# Zio_Ultrasonic_Distance_Sensor.net
KiCad netlist of a schematic drawn in EAGLE
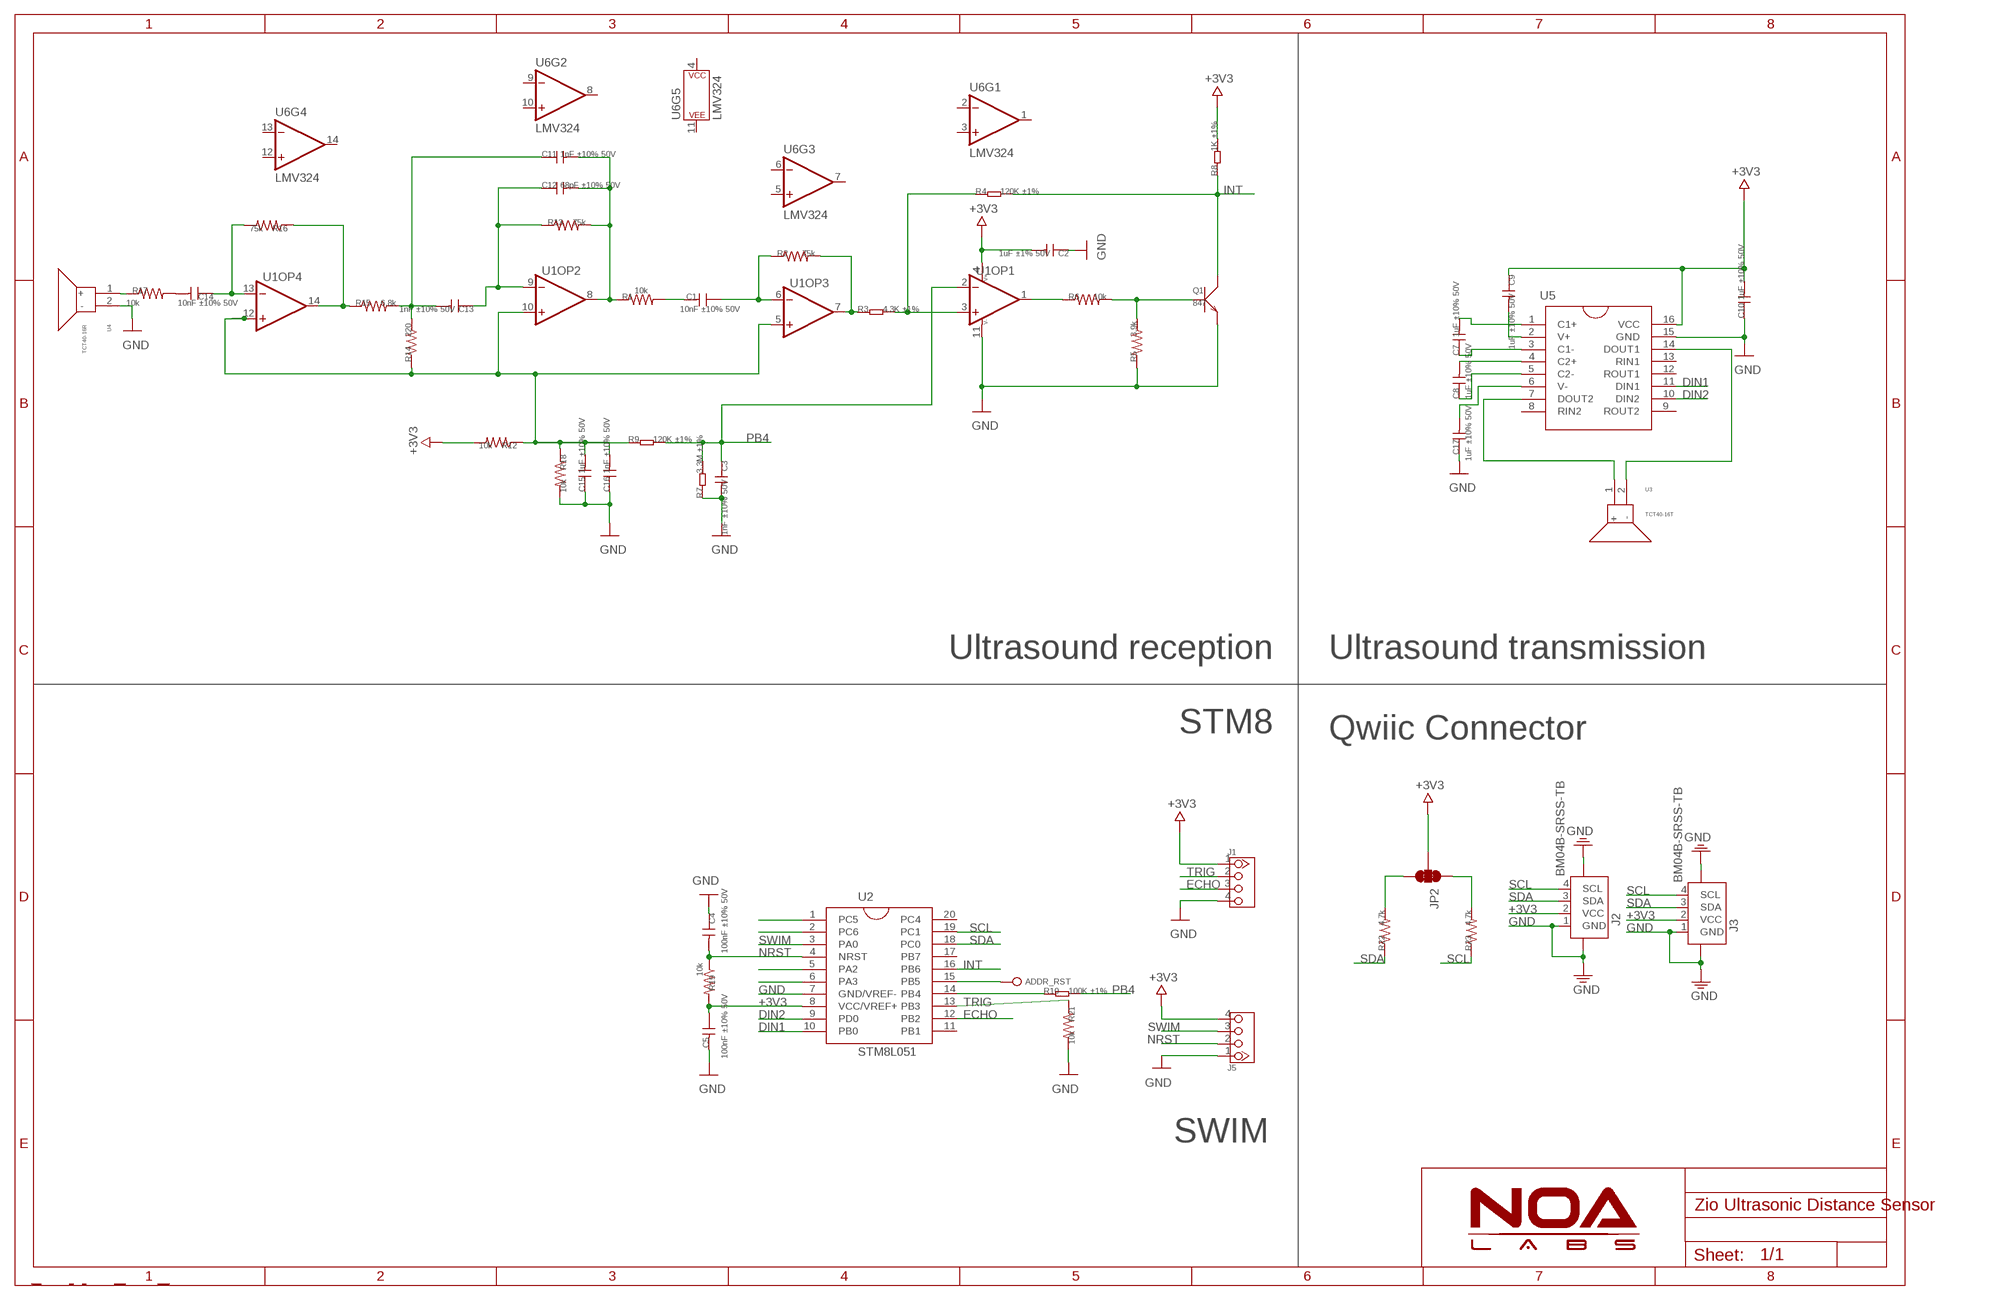
[diagram p0: schematic, sheet 1]

(export (version "E")
  (design (tool "Eeschema 10.0.6"))
  (components
    (comp (ref "ADDR_RST")
      (value "TEST_POINT35MIL")
      (footprint "eagle-import:1P-35MIL")
      (libsource (lib "eagle-import") (part "TEST_POINT35MIL"))
    )
    (comp (ref "C1")
      (value "10nF ±10% 50V")
      (footprint "eagle-import:0603")
      (libsource (lib "eagle-import") (part "C-0603"))
    )
    (comp (ref "C2")
      (value "1uF ±1% 50V")
      (footprint "eagle-import:0603")
      (libsource (lib "eagle-import") (part "C-0603"))
    )
    (comp (ref "C3")
      (value "1nF ±10% 50V")
      (footprint "eagle-import:0603")
      (libsource (lib "eagle-import") (part "C-0603"))
    )
    (comp (ref "C4")
      (value "100nF ±10% 50V")
      (footprint "eagle-import:0603")
      (libsource (lib "eagle-import") (part "C-0603"))
    )
    (comp (ref "C5")
      (value "100nF ±10% 50V")
      (footprint "eagle-import:0603")
      (libsource (lib "eagle-import") (part "C-0603"))
    )
    (comp (ref "C7")
      (value "1uF ±10% 50V")
      (footprint "eagle-import:0603")
      (libsource (lib "eagle-import") (part "C-0603"))
    )
    (comp (ref "C8")
      (value "1uF ±10% 50V")
      (footprint "eagle-import:0603")
      (libsource (lib "eagle-import") (part "C-0603"))
    )
    (comp (ref "C9")
      (value "1uF ±10% 50V")
      (footprint "eagle-import:0603")
      (libsource (lib "eagle-import") (part "C-0603"))
    )
    (comp (ref "C10")
      (value "1uF ±10% 50V")
      (footprint "eagle-import:0603")
      (libsource (lib "eagle-import") (part "C-0603"))
    )
    (comp (ref "C11")
      (value "1nF ±10% 50V")
      (footprint "eagle-import:0603")
      (libsource (lib "eagle-import") (part "C-0603"))
    )
    (comp (ref "C12")
      (value "68pF ±10% 50V")
      (footprint "eagle-import:0603")
      (libsource (lib "eagle-import") (part "C-0603"))
    )
    (comp (ref "C13")
      (value "1nF ±10% 50V")
      (footprint "eagle-import:0603")
      (libsource (lib "eagle-import") (part "C-0603"))
    )
    (comp (ref "C14")
      (value "10nF ±10% 50V")
      (footprint "eagle-import:0603")
      (libsource (lib "eagle-import") (part "C-0603"))
    )
    (comp (ref "C15")
      (value "1uF ±10% 50V")
      (footprint "eagle-import:0603")
      (libsource (lib "eagle-import") (part "C-0603"))
    )
    (comp (ref "C16")
      (value "1nF ±10% 50V")
      (footprint "eagle-import:0603")
      (libsource (lib "eagle-import") (part "C-0603"))
    )
    (comp (ref "C17")
      (value "1uF ±10% 50V")
      (footprint "eagle-import:0603")
      (libsource (lib "eagle-import") (part "C-0603"))
    )
    (comp (ref "J1")
      (value "HEADER-4P-60/35MIL")
      (footprint "eagle-import:4P-65_35MIL")
      (libsource (lib "eagle-import") (part "HEADER-4P-60/35MIL"))
    )
    (comp (ref "J2")
      (value "BM04B-SRSS-TB")
      (footprint "eagle-import:JST-SH-4P-90")
      (libsource (lib "eagle-import") (part "JST-SH-4P"))
    )
    (comp (ref "J3")
      (value "BM04B-SRSS-TB")
      (footprint "eagle-import:JST-SH-4P-90")
      (libsource (lib "eagle-import") (part "JST-SH-4P"))
    )
    (comp (ref "J5")
      (value "HEADER-4P-TEST_3.08_4P")
      (footprint "eagle-import:TEST_3.08_4P")
      (libsource (lib "eagle-import") (part "HEADER-4P-TEST_3.08_4P"))
    )
    (comp (ref "JP2")
      (value "SMT-JUMPER_3_2-NC_TRACE")
      (footprint "eagle-import:SMT-JUMPER_3_2-NC_TRACE")
      (libsource (lib "eagle-import") (part "SMT-JUMPER_3_2-NC_TRACE"))
    )
    (comp (ref "Q1")
      (value "847")
      (footprint "eagle-import:SOT23")
      (libsource (lib "eagle-import") (part "TRANSISTOR-NPN-SOT23''"))
    )
    (comp (ref "R1")
      (value "10k")
      (footprint "eagle-import:0603")
      (libsource (lib "eagle-import") (part "10KOHM-0603-1/10W-1%"))
    )
    (comp (ref "R2")
      (value "75k")
      (footprint "eagle-import:0603")
      (libsource (lib "eagle-import") (part "75KOHM-0603-1/10W-1%"))
    )
    (comp (ref "R3")
      (value "4.3K ±1%")
      (footprint "eagle-import:0603")
      (libsource (lib "eagle-import") (part "R-0603"))
    )
    (comp (ref "R4")
      (value "120K ±1%")
      (footprint "eagle-import:0603")
      (libsource (lib "eagle-import") (part "R-0603"))
    )
    (comp (ref "R5")
      (value "3.9k")
      (footprint "eagle-import:0603")
      (libsource (lib "eagle-import") (part "3.9KOHM-0603-1/10W-1%"))
    )
    (comp (ref "R6")
      (value "10k")
      (footprint "eagle-import:0603")
      (libsource (lib "eagle-import") (part "10KOHM-0603-1/10W-1%"))
    )
    (comp (ref "R7")
      (value "3.3M ±1%")
      (footprint "eagle-import:0603")
      (libsource (lib "eagle-import") (part "R-0603"))
    )
    (comp (ref "R8")
      (value "1K ±1%")
      (footprint "eagle-import:0603")
      (libsource (lib "eagle-import") (part "R-0603"))
    )
    (comp (ref "R9")
      (value "120K ±1%")
      (footprint "eagle-import:0603")
      (libsource (lib "eagle-import") (part "R-0603"))
    )
    (comp (ref "R10")
      (value "100K ±1%")
      (footprint "eagle-import:0603")
      (libsource (lib "eagle-import") (part "R-0603"))
    )
    (comp (ref "R12")
      (value "10k")
      (footprint "eagle-import:0603")
      (libsource (lib "eagle-import") (part "10KOHM-0603-1/10W-1%"))
    )
    (comp (ref "R13")
      (value "75k")
      (footprint "eagle-import:0603")
      (libsource (lib "eagle-import") (part "75KOHM-0603-1/10W-1%"))
    )
    (comp (ref "R14")
      (value "220")
      (footprint "eagle-import:0603")
      (libsource (lib "eagle-import") (part "220OHM-0603-1/10W-1%"))
    )
    (comp (ref "R15")
      (value "6.8k")
      (footprint "eagle-import:0603")
      (libsource (lib "eagle-import") (part "6.8KOHM-0603-1/10W-1%"))
    )
    (comp (ref "R16")
      (value "75k")
      (footprint "eagle-import:0603")
      (libsource (lib "eagle-import") (part "75KOHM-0603-1/10W-1%"))
    )
    (comp (ref "R17")
      (value "10k")
      (footprint "eagle-import:0603")
      (libsource (lib "eagle-import") (part "10KOHM-0603-1/10W-1%"))
    )
    (comp (ref "R18")
      (value "10k")
      (footprint "eagle-import:0603")
      (libsource (lib "eagle-import") (part "10KOHM-0603-1/10W-1%"))
    )
    (comp (ref "R19")
      (value "10k")
      (footprint "eagle-import:0603")
      (libsource (lib "eagle-import") (part "10KOHM-0603-1/10W-1%"))
    )
    (comp (ref "R21")
      (value "10k")
      (footprint "eagle-import:0603")
      (libsource (lib "eagle-import") (part "10KOHM-0603-1/10W-1%"))
    )
    (comp (ref "R22")
      (value "4.7k")
      (footprint "eagle-import:0603")
      (libsource (lib "eagle-import") (part "4.7KOHM-0603-1/10W-1%"))
    )
    (comp (ref "R23")
      (value "4.7k")
      (footprint "eagle-import:0603")
      (libsource (lib "eagle-import") (part "4.7KOHM-0603-1/10W-1%"))
    )
    (comp (ref "U1")
      (value "LMV324")
      (footprint "eagle-import:SO014")
      (libsource (lib "eagle-import") (part "LMV324"))
    )
    (comp (ref "U2")
      (value "STM8L051")
      (footprint "eagle-import:TSSOP20")
      (libsource (lib "eagle-import") (part "STM8L051"))
    )
    (comp (ref "U3")
      (value "TCT40-16T")
      (footprint "eagle-import:TCT40-16T_R")
      (libsource (lib "eagle-import") (part "TCT40-16T/R"))
    )
    (comp (ref "U4")
      (value "TCT40-16R")
      (footprint "eagle-import:TCT40-16T_R")
      (libsource (lib "eagle-import") (part "TCT40-16T/R"))
    )
    (comp (ref "U5")
      (value "UT3232G-S16-RSOIC-16")
      (footprint "eagle-import:SOIC16")
      (libsource (lib "eagle-import") (part "UT3232G-S16-RSOIC-16"))
    )
    (comp (ref "U6")
      (value "LMV324")
      (footprint "eagle-import:SO14")
      (libsource (lib "eagle-import") (part "SparkFun-IC-Amplifiers_LMV324"))
    )
  )
  (nets
    (net (code "1") (name "+3V3") (class "Default")
      (node (ref "C10") (pin "2") (pinfunction "2_2") (pintype "passive"))
      (node (ref "C2") (pin "2") (pinfunction "2_2") (pintype "passive"))
      (node (ref "C5") (pin "1") (pinfunction "1_1") (pintype "passive"))
      (node (ref "C9") (pin "1") (pinfunction "1_1") (pintype "passive"))
      (node (ref "J1") (pin "1") (pinfunction "P$1_1") (pintype "bidirectional"))
      (node (ref "J2") (pin "2") (pinfunction "VCC_2") (pintype "bidirectional"))
      (node (ref "J3") (pin "2") (pinfunction "VCC_2") (pintype "bidirectional"))
      (node (ref "J5") (pin "4") (pinfunction "P$4_4") (pintype "bidirectional"))
      (node (ref "JP2") (pin "2") (pinfunction "2_2") (pintype "passive"))
      (node (ref "R12") (pin "2") (pinfunction "2_2") (pintype "passive"))
      (node (ref "R19") (pin "2") (pinfunction "2_2") (pintype "passive"))
      (node (ref "R8") (pin "2") (pinfunction "2_2") (pintype "passive"))
      (node (ref "U1") (pin "4") (pinfunction "V+_4") (pintype "power_in"))
      (node (ref "U2") (pin "8") (pinfunction "VCC/VREF+_8") (pintype "bidirectional"))
      (node (ref "U5") (pin "16") (pinfunction "VCC_16") (pintype "bidirectional"))
    )
    (net (code "2") (name "/DIN1") (class "Default")
      (node (ref "U2") (pin "10") (pinfunction "PB0_10") (pintype "bidirectional"))
      (node (ref "U5") (pin "11") (pinfunction "DIN1_11") (pintype "bidirectional"))
    )
    (net (code "3") (name "/DIN2") (class "Default")
      (node (ref "U2") (pin "9") (pinfunction "PD0_9") (pintype "bidirectional"))
      (node (ref "U5") (pin "10") (pinfunction "DIN2_10") (pintype "bidirectional"))
    )
    (net (code "4") (name "/ECHO") (class "Default")
      (node (ref "J1") (pin "3") (pinfunction "P$3_3") (pintype "bidirectional"))
      (node (ref "U2") (pin "12") (pinfunction "PB2_12") (pintype "bidirectional"))
    )
    (net (code "5") (name "/INT") (class "Default")
      (node (ref "Q1") (pin "3") (pinfunction "C_3") (pintype "passive"))
      (node (ref "R4") (pin "2") (pinfunction "2_2") (pintype "passive"))
      (node (ref "R8") (pin "1") (pinfunction "1_1") (pintype "passive"))
      (node (ref "U2") (pin "16") (pinfunction "PB6_16") (pintype "bidirectional"))
    )
    (net (code "6") (name "/NRST") (class "Default")
      (node (ref "C4") (pin "2") (pinfunction "2_2") (pintype "passive"))
      (node (ref "J5") (pin "2") (pinfunction "P$2_2") (pintype "bidirectional"))
      (node (ref "R19") (pin "1") (pinfunction "1_1") (pintype "passive"))
      (node (ref "U2") (pin "4") (pinfunction "NRST_4") (pintype "bidirectional"))
    )
    (net (code "7") (name "/PB4") (class "Default")
      (node (ref "C3") (pin "1") (pinfunction "1_1") (pintype "passive"))
      (node (ref "R10") (pin "2") (pinfunction "2_2") (pintype "passive"))
      (node (ref "R7") (pin "2") (pinfunction "2_2") (pintype "passive"))
      (node (ref "R9") (pin "2") (pinfunction "2_2") (pintype "passive"))
      (node (ref "U1") (pin "2") (pinfunction "IN-_2") (pintype "input"))
    )
    (net (code "8") (name "/SCL") (class "Default")
      (node (ref "J2") (pin "4") (pinfunction "SCL_4") (pintype "bidirectional"))
      (node (ref "J3") (pin "4") (pinfunction "SCL_4") (pintype "bidirectional"))
      (node (ref "R23") (pin "1") (pinfunction "1_1") (pintype "passive"))
      (node (ref "U2") (pin "19") (pinfunction "PC1_19") (pintype "bidirectional"))
    )
    (net (code "9") (name "/SDA") (class "Default")
      (node (ref "J2") (pin "3") (pinfunction "SDA_3") (pintype "bidirectional"))
      (node (ref "J3") (pin "3") (pinfunction "SDA_3") (pintype "bidirectional"))
      (node (ref "R22") (pin "1") (pinfunction "1_1") (pintype "passive"))
      (node (ref "U2") (pin "18") (pinfunction "PC0_18") (pintype "bidirectional"))
    )
    (net (code "10") (name "/SWIM") (class "Default")
      (node (ref "J5") (pin "3") (pinfunction "P$3_3") (pintype "bidirectional"))
      (node (ref "U2") (pin "3") (pinfunction "PA0_3") (pintype "bidirectional"))
    )
    (net (code "11") (name "/TRIG") (class "Default")
      (node (ref "J1") (pin "2") (pinfunction "P$2_2") (pintype "bidirectional"))
      (node (ref "R21") (pin "1") (pinfunction "1_1") (pintype "passive"))
      (node (ref "U2") (pin "13") (pinfunction "PB3_13") (pintype "bidirectional"))
    )
    (net (code "12") (name "GND") (class "Default")
      (node (ref "C10") (pin "1") (pinfunction "1_1") (pintype "passive"))
      (node (ref "C15") (pin "1") (pinfunction "1_1") (pintype "passive"))
      (node (ref "C16") (pin "1") (pinfunction "1_1") (pintype "passive"))
      (node (ref "C17") (pin "1") (pinfunction "1_1") (pintype "passive"))
      (node (ref "C2") (pin "1") (pinfunction "1_1") (pintype "passive"))
      (node (ref "C3") (pin "2") (pinfunction "2_2") (pintype "passive"))
      (node (ref "C4") (pin "1") (pinfunction "1_1") (pintype "passive"))
      (node (ref "C5") (pin "2") (pinfunction "2_2") (pintype "passive"))
      (node (ref "J1") (pin "4") (pinfunction "P$4_4") (pintype "bidirectional"))
      (node (ref "J2") (pin "1") (pinfunction "GND_1") (pintype "bidirectional"))
      (node (ref "J2") (pin "5") (pinfunction "5_5") (pintype "bidirectional"))
      (node (ref "J2") (pin "6") (pinfunction "6_6") (pintype "bidirectional"))
      (node (ref "J3") (pin "1") (pinfunction "GND_1") (pintype "bidirectional"))
      (node (ref "J3") (pin "5") (pinfunction "5_5") (pintype "bidirectional"))
      (node (ref "J3") (pin "6") (pinfunction "6_6") (pintype "bidirectional"))
      (node (ref "J5") (pin "1") (pinfunction "P$1_1") (pintype "bidirectional"))
      (node (ref "Q1") (pin "2") (pinfunction "E_2") (pintype "passive"))
      (node (ref "R18") (pin "2") (pinfunction "2_2") (pintype "passive"))
      (node (ref "R21") (pin "2") (pinfunction "2_2") (pintype "passive"))
      (node (ref "R5") (pin "1") (pinfunction "1_1") (pintype "passive"))
      (node (ref "R7") (pin "1") (pinfunction "1_1") (pintype "passive"))
      (node (ref "U1") (pin "11") (pinfunction "V-_11") (pintype "power_in"))
      (node (ref "U2") (pin "7") (pinfunction "GND/VREF-_7") (pintype "bidirectional"))
      (node (ref "U4") (pin "2") (pinfunction "-_2") (pintype "bidirectional"))
      (node (ref "U5") (pin "15") (pinfunction "GND_15") (pintype "bidirectional"))
    )
    (net (code "13") (name "Net-(ADDR_RST-1)") (class "Default")
      (node (ref "ADDR_RST") (pin "P$1") (pinfunction "1_P$1") (pintype "bidirectional"))
      (node (ref "U2") (pin "15") (pinfunction "PB5_15") (pintype "bidirectional"))
    )
    (net (code "14") (name "Net-(C1-Pad2)") (class "Default")
      (node (ref "C1") (pin "2") (pinfunction "2_2") (pintype "passive"))
      (node (ref "R1") (pin "2") (pinfunction "2_2") (pintype "passive"))
    )
    (net (code "15") (name "Net-(C11-Pad1)") (class "Default")
      (node (ref "C11") (pin "1") (pinfunction "1_1") (pintype "passive"))
      (node (ref "C13") (pin "2") (pinfunction "2_2") (pintype "passive"))
      (node (ref "R14") (pin "2") (pinfunction "2_2") (pintype "passive"))
      (node (ref "R15") (pin "2") (pinfunction "2_2") (pintype "passive"))
    )
    (net (code "16") (name "Net-(C14-Pad2)") (class "Default")
      (node (ref "C14") (pin "2") (pinfunction "2_2") (pintype "passive"))
      (node (ref "R17") (pin "2") (pinfunction "2_2") (pintype "passive"))
    )
    (net (code "17") (name "Net-(JP2-Pad1)") (class "Default")
      (node (ref "JP2") (pin "1") (pinfunction "1_1") (pintype "passive"))
      (node (ref "R23") (pin "2") (pinfunction "2_2") (pintype "passive"))
    )
    (net (code "18") (name "Net-(JP2-Pad3)") (class "Default")
      (node (ref "JP2") (pin "3") (pinfunction "3_3") (pintype "passive"))
      (node (ref "R22") (pin "2") (pinfunction "2_2") (pintype "passive"))
    )
    (net (code "19") (name "Net-(Q1-B)") (class "Default")
      (node (ref "Q1") (pin "1") (pinfunction "B_1") (pintype "passive"))
      (node (ref "R5") (pin "2") (pinfunction "2_2") (pintype "passive"))
      (node (ref "R6") (pin "2") (pinfunction "2_2") (pintype "passive"))
    )
    (net (code "20") (name "Net-(U1A-IN+)") (class "Default")
      (node (ref "R3") (pin "2") (pinfunction "2_2") (pintype "passive"))
      (node (ref "R4") (pin "1") (pinfunction "1_1") (pintype "passive"))
      (node (ref "U1") (pin "3") (pinfunction "IN+_3") (pintype "input"))
    )
    (net (code "21") (name "Net-(U1A-OUT)") (class "Default")
      (node (ref "R6") (pin "1") (pinfunction "1_1") (pintype "passive"))
      (node (ref "U1") (pin "1") (pinfunction "OUT_1") (pintype "output"))
    )
    (net (code "22") (name "Net-(U1B-IN+)") (class "Default")
      (node (ref "C15") (pin "2") (pinfunction "2_2") (pintype "passive"))
      (node (ref "C16") (pin "2") (pinfunction "2_2") (pintype "passive"))
      (node (ref "R12") (pin "1") (pinfunction "1_1") (pintype "passive"))
      (node (ref "R14") (pin "1") (pinfunction "1_1") (pintype "passive"))
      (node (ref "R18") (pin "1") (pinfunction "1_1") (pintype "passive"))
      (node (ref "R9") (pin "1") (pinfunction "1_1") (pintype "passive"))
      (node (ref "U1") (pin "10") (pinfunction "IN+_10") (pintype "input"))
      (node (ref "U1") (pin "12") (pinfunction "IN+_12") (pintype "input"))
      (node (ref "U1") (pin "5") (pinfunction "IN+_5") (pintype "input"))
    )
    (net (code "23") (name "Net-(U1B-IN-)") (class "Default")
      (node (ref "C12") (pin "1") (pinfunction "1_1") (pintype "passive"))
      (node (ref "C13") (pin "1") (pinfunction "1_1") (pintype "passive"))
      (node (ref "R13") (pin "1") (pinfunction "1_1") (pintype "passive"))
      (node (ref "U1") (pin "9") (pinfunction "IN-_9") (pintype "input"))
    )
    (net (code "24") (name "Net-(U1B-OUT)") (class "Default")
      (node (ref "C11") (pin "2") (pinfunction "2_2") (pintype "passive"))
      (node (ref "C12") (pin "2") (pinfunction "2_2") (pintype "passive"))
      (node (ref "R1") (pin "1") (pinfunction "1_1") (pintype "passive"))
      (node (ref "R13") (pin "2") (pinfunction "2_2") (pintype "passive"))
      (node (ref "U1") (pin "8") (pinfunction "OUT_8") (pintype "output"))
    )
    (net (code "25") (name "Net-(U1C-IN-)") (class "Default")
      (node (ref "C1") (pin "1") (pinfunction "1_1") (pintype "passive"))
      (node (ref "R2") (pin "1") (pinfunction "1_1") (pintype "passive"))
      (node (ref "U1") (pin "6") (pinfunction "IN-_6") (pintype "input"))
    )
    (net (code "26") (name "Net-(U1C-OUT)") (class "Default")
      (node (ref "R2") (pin "2") (pinfunction "2_2") (pintype "passive"))
      (node (ref "R3") (pin "1") (pinfunction "1_1") (pintype "passive"))
      (node (ref "U1") (pin "7") (pinfunction "OUT_7") (pintype "output"))
    )
    (net (code "27") (name "Net-(U1D-IN-)") (class "Default")
      (node (ref "C14") (pin "1") (pinfunction "1_1") (pintype "passive"))
      (node (ref "R16") (pin "2") (pinfunction "2_2") (pintype "passive"))
      (node (ref "U1") (pin "13") (pinfunction "IN-_13") (pintype "input"))
    )
    (net (code "28") (name "Net-(U1D-OUT)") (class "Default")
      (node (ref "R15") (pin "1") (pinfunction "1_1") (pintype "passive"))
      (node (ref "R16") (pin "1") (pinfunction "1_1") (pintype "passive"))
      (node (ref "U1") (pin "14") (pinfunction "OUT_14") (pintype "output"))
    )
    (net (code "29") (name "Net-(U2-PB4)") (class "Default")
      (node (ref "R10") (pin "1") (pinfunction "1_1") (pintype "passive"))
      (node (ref "U2") (pin "14") (pinfunction "PB4_14") (pintype "bidirectional"))
    )
    (net (code "30") (name "Net-(U3-+)") (class "Default")
      (node (ref "U3") (pin "1") (pinfunction "+_1") (pintype "bidirectional"))
      (node (ref "U5") (pin "7") (pinfunction "DOUT2_7") (pintype "bidirectional"))
    )
    (net (code "31") (name "Net-(U3--)") (class "Default")
      (node (ref "U3") (pin "2") (pinfunction "-_2") (pintype "bidirectional"))
      (node (ref "U5") (pin "14") (pinfunction "DOUT1_14") (pintype "bidirectional"))
    )
    (net (code "32") (name "Net-(U4-+)") (class "Default")
      (node (ref "R17") (pin "1") (pinfunction "1_1") (pintype "passive"))
      (node (ref "U4") (pin "1") (pinfunction "+_1") (pintype "bidirectional"))
    )
    (net (code "33") (name "Net-(U5-C1+)") (class "Default")
      (node (ref "C7") (pin "2") (pinfunction "2_2") (pintype "passive"))
      (node (ref "U5") (pin "1") (pinfunction "C1+_1") (pintype "bidirectional"))
    )
    (net (code "34") (name "Net-(U5-C1-)") (class "Default")
      (node (ref "C7") (pin "1") (pinfunction "1_1") (pintype "passive"))
      (node (ref "U5") (pin "3") (pinfunction "C1-_3") (pintype "bidirectional"))
    )
    (net (code "35") (name "Net-(U5-C2+)") (class "Default")
      (node (ref "C8") (pin "2") (pinfunction "2_2") (pintype "passive"))
      (node (ref "U5") (pin "4") (pinfunction "C2+_4") (pintype "bidirectional"))
    )
    (net (code "36") (name "Net-(U5-C2-)") (class "Default")
      (node (ref "C8") (pin "1") (pinfunction "1_1") (pintype "passive"))
      (node (ref "U5") (pin "5") (pinfunction "C2-_5") (pintype "bidirectional"))
    )
    (net (code "37") (name "Net-(U5-V+)") (class "Default")
      (node (ref "C9") (pin "2") (pinfunction "2_2") (pintype "passive"))
      (node (ref "U5") (pin "2") (pinfunction "V+_2") (pintype "bidirectional"))
    )
    (net (code "38") (name "Net-(U5-V-)") (class "Default")
      (node (ref "C17") (pin "2") (pinfunction "2_2") (pintype "passive"))
      (node (ref "U5") (pin "6") (pinfunction "V-_6") (pintype "bidirectional"))
    )
    (net (code "39") (name "unconnected-(U2-PA2-Pad5)") (class "Default")
      (node (ref "U2") (pin "5") (pinfunction "PA2_5") (pintype "bidirectional"))
    )
    (net (code "40") (name "unconnected-(U2-PA3-Pad6)") (class "Default")
      (node (ref "U2") (pin "6") (pinfunction "PA3_6") (pintype "bidirectional"))
    )
    (net (code "41") (name "unconnected-(U2-PB1-Pad11)") (class "Default")
      (node (ref "U2") (pin "11") (pinfunction "PB1_11") (pintype "bidirectional"))
    )
    (net (code "42") (name "unconnected-(U2-PB7-Pad17)") (class "Default")
      (node (ref "U2") (pin "17") (pinfunction "PB7_17") (pintype "bidirectional"))
    )
    (net (code "43") (name "unconnected-(U2-PC4-Pad20)") (class "Default")
      (node (ref "U2") (pin "20") (pinfunction "PC4_20") (pintype "bidirectional"))
    )
    (net (code "44") (name "unconnected-(U2-PC5-Pad1)") (class "Default")
      (node (ref "U2") (pin "1") (pinfunction "PC5_1") (pintype "bidirectional"))
    )
    (net (code "45") (name "unconnected-(U2-PC6-Pad2)") (class "Default")
      (node (ref "U2") (pin "2") (pinfunction "PC6_2") (pintype "bidirectional"))
    )
    (net (code "46") (name "unconnected-(U5-RIN1-Pad13)") (class "Default")
      (node (ref "U5") (pin "13") (pinfunction "RIN1_13") (pintype "bidirectional"))
    )
    (net (code "47") (name "unconnected-(U5-RIN2-Pad8)") (class "Default")
      (node (ref "U5") (pin "8") (pinfunction "RIN2_8") (pintype "bidirectional"))
    )
    (net (code "48") (name "unconnected-(U5-ROUT1-Pad12)") (class "Default")
      (node (ref "U5") (pin "12") (pinfunction "ROUT1_12") (pintype "bidirectional"))
    )
    (net (code "49") (name "unconnected-(U5-ROUT2-Pad9)") (class "Default")
      (node (ref "U5") (pin "9") (pinfunction "ROUT2_9") (pintype "bidirectional"))
    )
    (net (code "50") (name "unconnected-(U6A-+IN-Pad3)") (class "Default")
      (node (ref "U6") (pin "3") (pinfunction "+IN_3") (pintype "input"))
    )
    (net (code "51") (name "unconnected-(U6A--IN-Pad2)") (class "Default")
      (node (ref "U6") (pin "2") (pinfunction "-IN_2") (pintype "input"))
    )
    (net (code "52") (name "unconnected-(U6A-OUT-Pad1)") (class "Default")
      (node (ref "U6") (pin "1") (pinfunction "OUT_1") (pintype "output"))
    )
    (net (code "53") (name "unconnected-(U6B-+IN-Pad10)") (class "Default")
      (node (ref "U6") (pin "10") (pinfunction "+IN_10") (pintype "input"))
    )
    (net (code "54") (name "unconnected-(U6B--IN-Pad9)") (class "Default")
      (node (ref "U6") (pin "9") (pinfunction "-IN_9") (pintype "input"))
    )
    (net (code "55") (name "unconnected-(U6B-OUT-Pad8)") (class "Default")
      (node (ref "U6") (pin "8") (pinfunction "OUT_8") (pintype "output"))
    )
    (net (code "56") (name "unconnected-(U6C-+IN-Pad5)") (class "Default")
      (node (ref "U6") (pin "5") (pinfunction "+IN_5") (pintype "input"))
    )
    (net (code "57") (name "unconnected-(U6C--IN-Pad6)") (class "Default")
      (node (ref "U6") (pin "6") (pinfunction "-IN_6") (pintype "input"))
    )
    (net (code "58") (name "unconnected-(U6C-OUT-Pad7)") (class "Default")
      (node (ref "U6") (pin "7") (pinfunction "OUT_7") (pintype "output"))
    )
    (net (code "59") (name "unconnected-(U6D-+IN-Pad12)") (class "Default")
      (node (ref "U6") (pin "12") (pinfunction "+IN_12") (pintype "input"))
    )
    (net (code "60") (name "unconnected-(U6D--IN-Pad13)") (class "Default")
      (node (ref "U6") (pin "13") (pinfunction "-IN_13") (pintype "input"))
    )
    (net (code "61") (name "unconnected-(U6D-OUT-Pad14)") (class "Default")
      (node (ref "U6") (pin "14") (pinfunction "OUT_14") (pintype "output"))
    )
    (net (code "62") (name "unconnected-(U6E-P$V+-Pad4)") (class "Default")
      (node (ref "U6") (pin "4") (pinfunction "P$V+_4") (pintype "bidirectional"))
    )
    (net (code "63") (name "unconnected-(U6E-P$V--Pad11)") (class "Default")
      (node (ref "U6") (pin "11") (pinfunction "P$V-_11") (pintype "bidirectional"))
    )
  )
)
